# iSENSE_Data_Logger.net
KiCad netlist of a schematic drawn in EAGLE
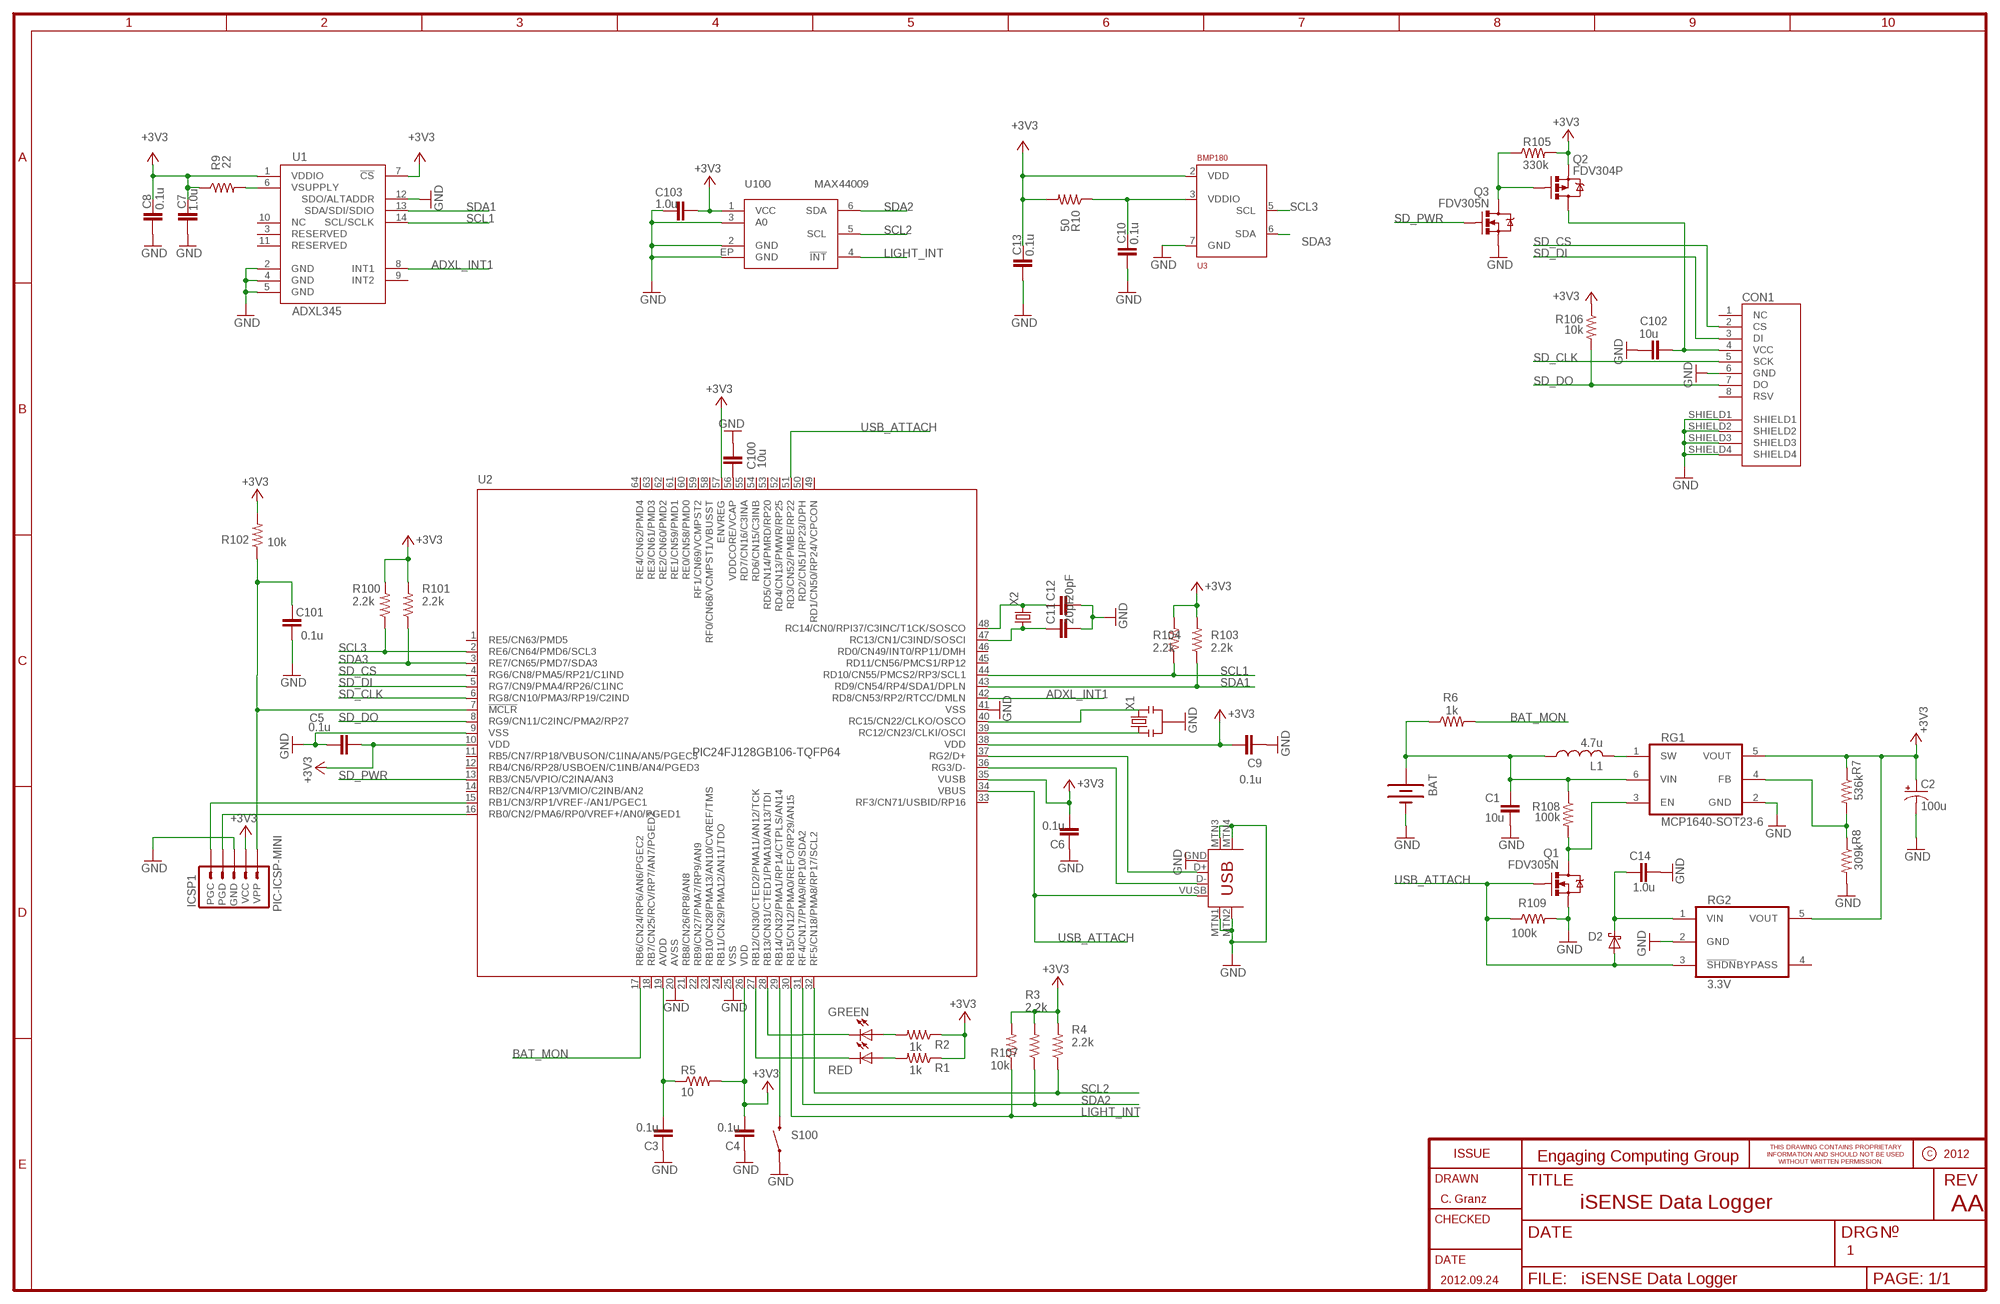
[diagram p0: schematic, sheet 1]

(export (version "E")
  (design (tool "Eeschema 10.0.6"))
  (components
    (comp (ref "BAT")
      (value "BATTERY-AAA-PCB-1-NO-HOLES")
      (footprint "eagle-import:BATTERY_HOLDER_AAA_KEYSTONE_2466_NO_HOLES")
      (libsource (lib "eagle-import") (part "BATTERY-AAA-PCB-1-NO-HOLES"))
    )
    (comp (ref "C1")
      (value "10u")
      (footprint "eagle-import:RCL_0603")
      (libsource (lib "eagle-import") (part "CAPACITOR-0603"))
    )
    (comp (ref "C2")
      (value "100u")
      (footprint "eagle-import:CT3528")
      (libsource (lib "eagle-import") (part "CPOL-USCT3528"))
    )
    (comp (ref "C3")
      (value "0.1u")
      (footprint "eagle-import:RCL_0402")
      (libsource (lib "eagle-import") (part "CAPACITOR-0402"))
    )
    (comp (ref "C4")
      (value "0.1u")
      (footprint "eagle-import:RCL_0402")
      (libsource (lib "eagle-import") (part "CAPACITOR-0402"))
    )
    (comp (ref "C5")
      (value "0.1u")
      (footprint "eagle-import:RCL_0402")
      (libsource (lib "eagle-import") (part "CAPACITOR-0402"))
    )
    (comp (ref "C6")
      (value "0.1u")
      (footprint "eagle-import:RCL_0402")
      (libsource (lib "eagle-import") (part "CAPACITOR-0402"))
    )
    (comp (ref "C7")
      (value "1.0u")
      (footprint "eagle-import:RCL_0402")
      (libsource (lib "eagle-import") (part "CAPACITOR-0402"))
    )
    (comp (ref "C8")
      (value "0.1u")
      (footprint "eagle-import:RCL_0402")
      (libsource (lib "eagle-import") (part "CAPACITOR-0402"))
    )
    (comp (ref "C9")
      (value "0.1u")
      (footprint "eagle-import:RCL_0402")
      (libsource (lib "eagle-import") (part "CAPACITOR-0402"))
    )
    (comp (ref "C10")
      (value "0.1u")
      (footprint "eagle-import:RCL_0402")
      (libsource (lib "eagle-import") (part "CAPACITOR-0402"))
    )
    (comp (ref "C11")
      (value "20pF")
      (footprint "eagle-import:RCL_0402")
      (libsource (lib "eagle-import") (part "CAPACITOR-0402"))
    )
    (comp (ref "C12")
      (value "20pF")
      (footprint "eagle-import:RCL_0402")
      (libsource (lib "eagle-import") (part "CAPACITOR-0402"))
    )
    (comp (ref "C13")
      (value "0.1u")
      (footprint "eagle-import:RCL_0402")
      (libsource (lib "eagle-import") (part "CAPACITOR-0402"))
    )
    (comp (ref "C14")
      (value "1.0u")
      (footprint "eagle-import:RCL_0603")
      (libsource (lib "eagle-import") (part "CAPACITOR-0603"))
    )
    (comp (ref "C100")
      (value "10u")
      (footprint "eagle-import:RCL_0603")
      (libsource (lib "eagle-import") (part "CAPACITOR-0603"))
    )
    (comp (ref "C101")
      (value "0.1u")
      (footprint "eagle-import:RCL_0402")
      (libsource (lib "eagle-import") (part "CAPACITOR-0402"))
    )
    (comp (ref "C102")
      (value "10u")
      (footprint "eagle-import:RCL_0402")
      (libsource (lib "eagle-import") (part "CAPACITOR-0402"))
    )
    (comp (ref "C103")
      (value "1.0u")
      (footprint "eagle-import:RCL_0402")
      (libsource (lib "eagle-import") (part "CAPACITOR-0402"))
    )
    (comp (ref "CON1")
      (value "SOCKET_SD_CARD_MICRO-AMP-101-00303-68")
      (footprint "eagle-import:SOCKET_SD_CARD_MICRO")
      (fields (field (name "PN") "101-00303-68"))
      (libsource (lib "eagle-import") (part "SOCKET_SD_CARD_MICRO-AMP-101-00303-68"))
    )
    (comp (ref "D2")
      (value "DIODE_SCHOTTKY-SOD523")
      (footprint "eagle-import:SOD523")
      (libsource (lib "eagle-import") (part "DIODE_SCHOTTKY-SOD523"))
    )
    (comp (ref "GREEN")
      (value "GREEN")
      (footprint "eagle-import:LED_0603")
      (libsource (lib "eagle-import") (part "LED-0603"))
    )
    (comp (ref "ICSP1")
      (value "PIC-ICSP-MINI")
      (footprint "eagle-import:PIC-ICSP-MINI")
      (libsource (lib "eagle-import") (part "PIC-ICSP-MINI"))
    )
    (comp (ref "L1")
      (value "4.7u")
      (footprint "eagle-import:INDUCTOR_3MM_X_3MM")
      (libsource (lib "eagle-import") (part "INDUCTOR-3X3MM"))
    )
    (comp (ref "Q1")
      (value "FDV305N")
      (footprint "eagle-import:SOT23-3")
      (fields (field (name "PN") "FDV305N"))
      (libsource (lib "eagle-import") (part "FDV305N"))
    )
    (comp (ref "Q2")
      (value "FDV304P")
      (footprint "eagle-import:SOT23-3")
      (fields (field (name "PN") "FDV304P"))
      (libsource (lib "eagle-import") (part "FDV302P"))
    )
    (comp (ref "Q3")
      (value "FDV305N")
      (footprint "eagle-import:SOT23-3")
      (fields (field (name "PN") "FDV305N"))
      (libsource (lib "eagle-import") (part "FDV305N"))
    )
    (comp (ref "R1")
      (value "1k")
      (footprint "eagle-import:RCL_0402")
      (libsource (lib "eagle-import") (part "RESISTOR-0402"))
    )
    (comp (ref "R2")
      (value "1k")
      (footprint "eagle-import:RCL_0402")
      (libsource (lib "eagle-import") (part "RESISTOR-0402"))
    )
    (comp (ref "R3")
      (value "2.2k")
      (footprint "eagle-import:RCL_0402")
      (libsource (lib "eagle-import") (part "RESISTOR-0402"))
    )
    (comp (ref "R4")
      (value "2.2k")
      (footprint "eagle-import:RCL_0402")
      (libsource (lib "eagle-import") (part "RESISTOR-0402"))
    )
    (comp (ref "R5")
      (value "10")
      (footprint "eagle-import:RCL_0402")
      (libsource (lib "eagle-import") (part "RESISTOR-0402"))
    )
    (comp (ref "R6")
      (value "1k")
      (footprint "eagle-import:RCL_0402")
      (libsource (lib "eagle-import") (part "RESISTOR-0402"))
    )
    (comp (ref "R7")
      (value "536k")
      (footprint "eagle-import:RCL_0402")
      (libsource (lib "eagle-import") (part "RESISTOR-0402"))
    )
    (comp (ref "R8")
      (value "309k")
      (footprint "eagle-import:RCL_0402")
      (libsource (lib "eagle-import") (part "RESISTOR-0402"))
    )
    (comp (ref "R9")
      (value "22")
      (footprint "eagle-import:RCL_0402")
      (libsource (lib "eagle-import") (part "RESISTOR-0402"))
    )
    (comp (ref "R10")
      (value "50")
      (footprint "eagle-import:RCL_0402")
      (libsource (lib "eagle-import") (part "RESISTOR-0402"))
    )
    (comp (ref "R100")
      (value "2.2k")
      (footprint "eagle-import:RCL_0402")
      (libsource (lib "eagle-import") (part "RESISTOR-0402"))
    )
    (comp (ref "R101")
      (value "2.2k")
      (footprint "eagle-import:RCL_0402")
      (libsource (lib "eagle-import") (part "RESISTOR-0402"))
    )
    (comp (ref "R102")
      (value "10k")
      (footprint "eagle-import:RCL_0402")
      (libsource (lib "eagle-import") (part "RESISTOR-0402"))
    )
    (comp (ref "R103")
      (value "2.2k")
      (footprint "eagle-import:RCL_0402")
      (libsource (lib "eagle-import") (part "RESISTOR-0402"))
    )
    (comp (ref "R104")
      (value "2.2k")
      (footprint "eagle-import:RCL_0402")
      (libsource (lib "eagle-import") (part "RESISTOR-0402"))
    )
    (comp (ref "R105")
      (value "330k")
      (footprint "eagle-import:RCL_0402")
      (libsource (lib "eagle-import") (part "RESISTOR-0402"))
    )
    (comp (ref "R106")
      (value "10k")
      (footprint "eagle-import:RCL_0402")
      (libsource (lib "eagle-import") (part "RESISTOR-0402"))
    )
    (comp (ref "R107")
      (value "10k")
      (footprint "eagle-import:RCL_0402")
      (libsource (lib "eagle-import") (part "RESISTOR-0402"))
    )
    (comp (ref "R108")
      (value "100k")
      (footprint "eagle-import:RCL_0402")
      (libsource (lib "eagle-import") (part "RESISTOR-0402"))
    )
    (comp (ref "R109")
      (value "100k")
      (footprint "eagle-import:RCL_0402")
      (libsource (lib "eagle-import") (part "RESISTOR-0402"))
    )
    (comp (ref "RED")
      (value "RED")
      (footprint "eagle-import:LED_0603")
      (libsource (lib "eagle-import") (part "LED-0603"))
    )
    (comp (ref "RG1")
      (value "MCP1640-SOT23-6")
      (footprint "eagle-import:SOT23-6")
      (libsource (lib "eagle-import") (part "MCP1640-SOT23-6"))
    )
    (comp (ref "RG2")
      (value "3.3V")
      (footprint "eagle-import:SOT23-5")
      (libsource (lib "eagle-import") (part "TC1015"))
    )
    (comp (ref "S100")
      (value "SWITCH_MOMENTARY-SMD-RA")
      (footprint "eagle-import:SWITCH_TACTILE_SMD_RA")
      (libsource (lib "eagle-import") (part "SWITCH_MOMENTARY-SMD-RA"))
    )
    (comp (ref "U1")
      (value "ADXL345")
      (footprint "eagle-import:LGA14")
      (libsource (lib "eagle-import") (part "ADXL345"))
    )
    (comp (ref "U2")
      (value "PIC24FJ128GB106-TQFP64")
      (footprint "eagle-import:TQFP64-10X10")
      (fields (field (name "PN") "PIC24FJ128GB106-I/PT"))
      (libsource (lib "eagle-import") (part "PIC24FJ128GB106-TQFP64"))
    )
    (comp (ref "U3")
      (value "BMP180")
      (footprint "eagle-import:LGA7")
      (libsource (lib "eagle-import") (part "BMP180"))
    )
    (comp (ref "U100")
      (value "MAX44009")
      (footprint "eagle-import:UTDFN-OPTO")
      (fields (field (name "PN") "MAX44009EDT+T"))
      (libsource (lib "eagle-import") (part "MAX44009"))
    )
    (comp (ref "USB100")
      (value "CON_USB_4_PIN-A_MALE")
      (footprint "eagle-import:CON_USB_A_MALE_CNC_TECH_1001-010-01001")
      (fields (field (name "PN") "1001-010-01001"))
      (libsource (lib "eagle-import") (part "CON_USB_4_PIN-A_MALE"))
    )
    (comp (ref "X1")
      (value "CERAMIC_RESONATOR_3_PIN-2MM_X_4.5MM")
      (footprint "eagle-import:CERAMIC_RESONATOR_MURATA_2X4.5")
      (libsource (lib "eagle-import") (part "CERAMIC_RESONATOR_3_PIN-2MM_X_4.5MM"))
    )
    (comp (ref "X2")
      (value "CRYSTAL_2_PIN-4.9MM_X_1.8MM")
      (footprint "eagle-import:CRYSTAL_ABRACON_ABS10")
      (libsource (lib "eagle-import") (part "CRYSTAL_2_PIN-4.9MM_X_1.8MM"))
    )
  )
  (nets
    (net (code "1") (name "+3V3") (class "Default")
      (node (ref "C103") (pin "1") (pinfunction "1_1") (pintype "passive"))
      (node (ref "C13") (pin "2") (pinfunction "2_2") (pintype "passive"))
      (node (ref "C2") (pin "+") (pinfunction "+_+") (pintype "passive"))
      (node (ref "C4") (pin "2") (pinfunction "2_2") (pintype "passive"))
      (node (ref "C5") (pin "1") (pinfunction "1_1") (pintype "passive"))
      (node (ref "C6") (pin "2") (pinfunction "2_2") (pintype "passive"))
      (node (ref "C7") (pin "2") (pinfunction "2_2") (pintype "passive"))
      (node (ref "C8") (pin "2") (pinfunction "2_2") (pintype "passive"))
      (node (ref "C9") (pin "1") (pinfunction "1_1") (pintype "passive"))
      (node (ref "ICSP1") (pin "2") (pinfunction "VCC_2") (pintype "passive"))
      (node (ref "Q2") (pin "2") (pinfunction "S_2") (pintype "passive"))
      (node (ref "R1") (pin "1") (pinfunction "1_1") (pintype "passive"))
      (node (ref "R10") (pin "2") (pinfunction "2_2") (pintype "passive"))
      (node (ref "R100") (pin "2") (pinfunction "2_2") (pintype "passive"))
      (node (ref "R101") (pin "2") (pinfunction "2_2") (pintype "passive"))
      (node (ref "R102") (pin "2") (pinfunction "2_2") (pintype "passive"))
      (node (ref "R103") (pin "2") (pinfunction "2_2") (pintype "passive"))
      (node (ref "R104") (pin "2") (pinfunction "2_2") (pintype "passive"))
      (node (ref "R105") (pin "2") (pinfunction "2_2") (pintype "passive"))
      (node (ref "R106") (pin "1") (pinfunction "1_1") (pintype "passive"))
      (node (ref "R107") (pin "2") (pinfunction "2_2") (pintype "passive"))
      (node (ref "R2") (pin "1") (pinfunction "1_1") (pintype "passive"))
      (node (ref "R3") (pin "2") (pinfunction "2_2") (pintype "passive"))
      (node (ref "R4") (pin "2") (pinfunction "2_2") (pintype "passive"))
      (node (ref "R5") (pin "2") (pinfunction "2_2") (pintype "passive"))
      (node (ref "R7") (pin "1") (pinfunction "1_1") (pintype "passive"))
      (node (ref "R9") (pin "1") (pinfunction "1_1") (pintype "passive"))
      (node (ref "RG1") (pin "5") (pinfunction "VOUT_5") (pintype "power_in"))
      (node (ref "RG2") (pin "5") (pinfunction "VOUT_5") (pintype "power_in"))
      (node (ref "U1") (pin "1") (pinfunction "VDDIO_1") (pintype "power_in"))
      (node (ref "U1") (pin "7") (pinfunction "~{CS}_7") (pintype "input"))
      (node (ref "U100") (pin "1") (pinfunction "VCC_1") (pintype "bidirectional"))
      (node (ref "U2") (pin "10") (pinfunction "VDD_10") (pintype "power_in"))
      (node (ref "U2") (pin "26") (pinfunction "VDD_26") (pintype "power_in"))
      (node (ref "U2") (pin "35") (pinfunction "VUSB_35") (pintype "bidirectional"))
      (node (ref "U2") (pin "38") (pinfunction "VDD_38") (pintype "power_in"))
      (node (ref "U2") (pin "57") (pinfunction "ENVREG_57") (pintype "bidirectional"))
      (node (ref "U3") (pin "2") (pinfunction "VDD_2") (pintype "power_in"))
    )
    (net (code "2") (name "/ADXL_INT1") (class "Default")
      (node (ref "U1") (pin "8") (pinfunction "INT1_8") (pintype "output"))
      (node (ref "U2") (pin "42") (pinfunction "RD8/CN53/RP2/RTCC/DMLN_42") (pintype "bidirectional"))
    )
    (net (code "3") (name "/BAT_MON") (class "Default")
      (node (ref "R6") (pin "2") (pinfunction "2_2") (pintype "passive"))
      (node (ref "U2") (pin "17") (pinfunction "RB6/CN24/RP6/AN6/PGEC2_17") (pintype "bidirectional"))
    )
    (net (code "4") (name "/LIGHT_INT") (class "Default")
      (node (ref "R107") (pin "1") (pinfunction "1_1") (pintype "passive"))
      (node (ref "U100") (pin "4") (pinfunction "~{INT}_4") (pintype "output"))
      (node (ref "U2") (pin "30") (pinfunction "RB15/CN12/PMA0/REFO/RP29/AN15_30") (pintype "bidirectional"))
    )
    (net (code "5") (name "/SCL1") (class "Default")
      (node (ref "R104") (pin "1") (pinfunction "1_1") (pintype "passive"))
      (node (ref "U1") (pin "14") (pinfunction "SCL/SCLK_14") (pintype "input"))
      (node (ref "U2") (pin "44") (pinfunction "RD10/CN55/PMCS2/RP3/SCL1_44") (pintype "bidirectional"))
    )
    (net (code "6") (name "/SCL2") (class "Default")
      (node (ref "R4") (pin "1") (pinfunction "1_1") (pintype "passive"))
      (node (ref "U100") (pin "5") (pinfunction "SCL_5") (pintype "input"))
      (node (ref "U2") (pin "32") (pinfunction "RF5/CN18/PMA8/RP17/SCL2_32") (pintype "bidirectional"))
    )
    (net (code "7") (name "/SCL3") (class "Default")
      (node (ref "R100") (pin "1") (pinfunction "1_1") (pintype "passive"))
      (node (ref "U2") (pin "2") (pinfunction "RE6/CN64/PMD6/SCL3_2") (pintype "bidirectional"))
      (node (ref "U3") (pin "5") (pinfunction "SCL_5") (pintype "bidirectional"))
    )
    (net (code "8") (name "/SDA1") (class "Default")
      (node (ref "R103") (pin "1") (pinfunction "1_1") (pintype "passive"))
      (node (ref "U1") (pin "13") (pinfunction "SDA/SDI/SDIO_13") (pintype "bidirectional"))
      (node (ref "U2") (pin "43") (pinfunction "RD9/CN54/RP4/SDA1/DPLN_43") (pintype "bidirectional"))
    )
    (net (code "9") (name "/SDA2") (class "Default")
      (node (ref "R3") (pin "1") (pinfunction "1_1") (pintype "passive"))
      (node (ref "U100") (pin "6") (pinfunction "SDA_6") (pintype "bidirectional"))
      (node (ref "U2") (pin "31") (pinfunction "RF4/CN17/PMA9/RP10/SDA2_31") (pintype "bidirectional"))
    )
    (net (code "10") (name "/SDA3") (class "Default")
      (node (ref "R101") (pin "1") (pinfunction "1_1") (pintype "passive"))
      (node (ref "U2") (pin "3") (pinfunction "RE7/CN65/PMD7/SDA3_3") (pintype "bidirectional"))
      (node (ref "U3") (pin "6") (pinfunction "SDA_6") (pintype "bidirectional"))
    )
    (net (code "11") (name "/SD_CLK") (class "Default")
      (node (ref "CON1") (pin "5") (pinfunction "SCK_5") (pintype "input"))
      (node (ref "U2") (pin "6") (pinfunction "RG8/CN10/PMA3/RP19/C2IND_6") (pintype "bidirectional"))
    )
    (net (code "12") (name "/SD_CS") (class "Default")
      (node (ref "CON1") (pin "2") (pinfunction "CS_2") (pintype "input"))
      (node (ref "U2") (pin "4") (pinfunction "RG6/CN8/PMA5/RP21/C1IND_4") (pintype "bidirectional"))
    )
    (net (code "13") (name "/SD_DI") (class "Default")
      (node (ref "CON1") (pin "3") (pinfunction "DI_3") (pintype "input"))
      (node (ref "U2") (pin "5") (pinfunction "RG7/CN9/PMA4/RP26/C1INC_5") (pintype "bidirectional"))
    )
    (net (code "14") (name "/SD_DO") (class "Default")
      (node (ref "CON1") (pin "7") (pinfunction "DO_7") (pintype "output"))
      (node (ref "R106") (pin "2") (pinfunction "2_2") (pintype "passive"))
      (node (ref "U2") (pin "8") (pinfunction "RG9/CN11/C2INC/PMA2/RP27_8") (pintype "bidirectional"))
    )
    (net (code "15") (name "/SD_PWR") (class "Default")
      (node (ref "Q3") (pin "1") (pinfunction "G_1") (pintype "passive"))
      (node (ref "U2") (pin "13") (pinfunction "RB3/CN5/VPIO/C2INA/AN3_13") (pintype "bidirectional"))
    )
    (net (code "16") (name "/USB_ATTACH") (class "Default")
      (node (ref "D2") (pin "A") (pinfunction "A_A") (pintype "passive"))
      (node (ref "Q1") (pin "1") (pinfunction "G_1") (pintype "passive"))
      (node (ref "R109") (pin "1") (pinfunction "1_1") (pintype "passive"))
      (node (ref "RG2") (pin "3") (pinfunction "~{SHDN}_3") (pintype "input"))
      (node (ref "U2") (pin "34") (pinfunction "VBUS_34") (pintype "bidirectional"))
      (node (ref "U2") (pin "51") (pinfunction "RD3/CN52/PMBE/RP22_51") (pintype "bidirectional"))
      (node (ref "USB100") (pin "VUSB") (pinfunction "VBUS_VUSB") (pintype "power_in"))
    )
    (net (code "17") (name "GND") (class "Default")
      (node (ref "BAT") (pin "-") (pinfunction "-_-") (pintype "power_in"))
      (node (ref "C1") (pin "2") (pinfunction "2_2") (pintype "passive"))
      (node (ref "C10") (pin "1") (pinfunction "1_1") (pintype "passive"))
      (node (ref "C100") (pin "2") (pinfunction "2_2") (pintype "passive"))
      (node (ref "C101") (pin "2") (pinfunction "2_2") (pintype "passive"))
      (node (ref "C102") (pin "1") (pinfunction "1_1") (pintype "passive"))
      (node (ref "C103") (pin "2") (pinfunction "2_2") (pintype "passive"))
      (node (ref "C11") (pin "2") (pinfunction "2_2") (pintype "passive"))
      (node (ref "C12") (pin "2") (pinfunction "2_2") (pintype "passive"))
      (node (ref "C13") (pin "1") (pinfunction "1_1") (pintype "passive"))
      (node (ref "C14") (pin "2") (pinfunction "2_2") (pintype "passive"))
      (node (ref "C2") (pin "-") (pinfunction "-_-") (pintype "passive"))
      (node (ref "C3") (pin "1") (pinfunction "1_1") (pintype "passive"))
      (node (ref "C4") (pin "1") (pinfunction "1_1") (pintype "passive"))
      (node (ref "C5") (pin "2") (pinfunction "2_2") (pintype "passive"))
      (node (ref "C6") (pin "1") (pinfunction "1_1") (pintype "passive"))
      (node (ref "C7") (pin "1") (pinfunction "1_1") (pintype "passive"))
      (node (ref "C8") (pin "1") (pinfunction "1_1") (pintype "passive"))
      (node (ref "C9") (pin "2") (pinfunction "2_2") (pintype "passive"))
      (node (ref "CON1") (pin "6") (pinfunction "GND_6") (pintype "power_in"))
      (node (ref "CON1") (pin "SHIELD1") (pinfunction "SHIELD1_SHIELD1") (pintype "passive"))
      (node (ref "CON1") (pin "SHIELD2") (pinfunction "SHIELD2_SHIELD2") (pintype "passive"))
      (node (ref "CON1") (pin "SHIELD3") (pinfunction "SHIELD3_SHIELD3") (pintype "passive"))
      (node (ref "CON1") (pin "SHIELD4") (pinfunction "SHIELD4_SHIELD4") (pintype "passive"))
      (node (ref "ICSP1") (pin "3") (pinfunction "GND_3") (pintype "passive"))
      (node (ref "Q1") (pin "2") (pinfunction "S_2") (pintype "passive"))
      (node (ref "Q3") (pin "2") (pinfunction "S_2") (pintype "passive"))
      (node (ref "R109") (pin "2") (pinfunction "2_2") (pintype "passive"))
      (node (ref "R8") (pin "2") (pinfunction "2_2") (pintype "passive"))
      (node (ref "RG1") (pin "2") (pinfunction "GND_2") (pintype "power_in"))
      (node (ref "RG2") (pin "2") (pinfunction "GND_2") (pintype "power_in"))
      (node (ref "S100") (pin "1") (pinfunction "1_1") (pintype "passive"))
      (node (ref "U1") (pin "12") (pinfunction "SDO/ALTADDR_12") (pintype "bidirectional"))
      (node (ref "U1") (pin "2") (pinfunction "GND_2") (pintype "power_in"))
      (node (ref "U1") (pin "4") (pinfunction "GND_4") (pintype "power_in"))
      (node (ref "U1") (pin "5") (pinfunction "GND_5") (pintype "power_in"))
      (node (ref "U100") (pin "2") (pinfunction "GND_2") (pintype "power_in"))
      (node (ref "U100") (pin "3") (pinfunction "A0_3") (pintype "bidirectional"))
      (node (ref "U100") (pin "EP") (pinfunction "GND_EP") (pintype "power_in"))
      (node (ref "U2") (pin "20") (pinfunction "AVSS_20") (pintype "power_in"))
      (node (ref "U2") (pin "25") (pinfunction "VSS_25") (pintype "power_in"))
      (node (ref "U2") (pin "41") (pinfunction "VSS_41") (pintype "power_in"))
      (node (ref "U2") (pin "9") (pinfunction "VSS_9") (pintype "power_in"))
      (node (ref "U3") (pin "7") (pinfunction "GND_7") (pintype "power_in"))
      (node (ref "USB100") (pin "GND") (pinfunction "GND_GND") (pintype "power_in"))
      (node (ref "USB100") (pin "MTN1") (pinfunction "MTN1_MTN1") (pintype "passive"))
      (node (ref "USB100") (pin "MTN2") (pinfunction "MTN2_MTN2") (pintype "passive"))
      (node (ref "USB100") (pin "MTN3") (pinfunction "MTN3_MTN3") (pintype "passive"))
      (node (ref "USB100") (pin "MTN4") (pinfunction "MTN4_MTN4") (pintype "passive"))
      (node (ref "X1") (pin "2") (pinfunction "2_2") (pintype "passive"))
    )
    (net (code "18") (name "Net-(CON1-VCC)") (class "Default")
      (node (ref "C102") (pin "2") (pinfunction "2_2") (pintype "passive"))
      (node (ref "CON1") (pin "4") (pinfunction "VCC_4") (pintype "power_in"))
      (node (ref "Q2") (pin "3") (pinfunction "D_3") (pintype "passive"))
    )
    (net (code "19") (name "Net-(GREEN-PadA)") (class "Default")
      (node (ref "GREEN") (pin "A") (pinfunction "A_A") (pintype "passive"))
      (node (ref "R2") (pin "2") (pinfunction "2_2") (pintype "passive"))
    )
    (net (code "20") (name "Net-(ICSP1-PGC)") (class "Default")
      (node (ref "ICSP1") (pin "5") (pinfunction "PGC_5") (pintype "passive"))
      (node (ref "U2") (pin "15") (pinfunction "RB1/CN3/RP1/VREF-/AN1/PGEC1_15") (pintype "bidirectional"))
    )
    (net (code "21") (name "Net-(ICSP1-PGD)") (class "Default")
      (node (ref "ICSP1") (pin "4") (pinfunction "PGD_4") (pintype "passive"))
      (node (ref "U2") (pin "16") (pinfunction "RB0/CN2/PMA6/RP0/VREF+/AN0/PGED1_16") (pintype "bidirectional"))
    )
    (net (code "22") (name "Net-(ICSP1-VPP)") (class "Default")
      (node (ref "C101") (pin "1") (pinfunction "1_1") (pintype "passive"))
      (node (ref "ICSP1") (pin "1") (pinfunction "VPP_1") (pintype "passive"))
      (node (ref "R102") (pin "1") (pinfunction "1_1") (pintype "passive"))
      (node (ref "U2") (pin "7") (pinfunction "~{MCLR}_7") (pintype "bidirectional"))
    )
    (net (code "23") (name "Net-(Q1-D)") (class "Default")
      (node (ref "Q1") (pin "3") (pinfunction "D_3") (pintype "passive"))
      (node (ref "R108") (pin "2") (pinfunction "2_2") (pintype "passive"))
      (node (ref "RG1") (pin "3") (pinfunction "EN_3") (pintype "input"))
    )
    (net (code "24") (name "Net-(Q2-G)") (class "Default")
      (node (ref "Q2") (pin "1") (pinfunction "G_1") (pintype "passive"))
      (node (ref "Q3") (pin "3") (pinfunction "D_3") (pintype "passive"))
      (node (ref "R105") (pin "1") (pinfunction "1_1") (pintype "passive"))
    )
    (net (code "25") (name "Net-(R1-Pad2)") (class "Default")
      (node (ref "R1") (pin "2") (pinfunction "2_2") (pintype "passive"))
      (node (ref "RED") (pin "A") (pinfunction "A_A") (pintype "passive"))
    )
    (net (code "26") (name "Net-(RG1-FB)") (class "Default")
      (node (ref "R7") (pin "2") (pinfunction "2_2") (pintype "passive"))
      (node (ref "R8") (pin "1") (pinfunction "1_1") (pintype "passive"))
      (node (ref "RG1") (pin "4") (pinfunction "FB_4") (pintype "input"))
    )
    (net (code "27") (name "Net-(RG1-SW)") (class "Default")
      (node (ref "L1") (pin "2") (pinfunction "2_2") (pintype "passive"))
      (node (ref "RG1") (pin "1") (pinfunction "SW_1") (pintype "passive"))
    )
    (net (code "28") (name "Net-(RG1-VIN)") (class "Default")
      (node (ref "BAT") (pin "+") (pinfunction "+_+") (pintype "power_in"))
      (node (ref "C1") (pin "1") (pinfunction "1_1") (pintype "passive"))
      (node (ref "L1") (pin "1") (pinfunction "1_1") (pintype "passive"))
      (node (ref "R108") (pin "1") (pinfunction "1_1") (pintype "passive"))
      (node (ref "R6") (pin "1") (pinfunction "1_1") (pintype "passive"))
      (node (ref "RG1") (pin "6") (pinfunction "VIN_6") (pintype "power_in"))
    )
    (net (code "29") (name "Net-(RG2-VIN)") (class "Default")
      (node (ref "C14") (pin "1") (pinfunction "1_1") (pintype "passive"))
      (node (ref "D2") (pin "C") (pinfunction "C_C") (pintype "passive"))
      (node (ref "RG2") (pin "1") (pinfunction "VIN_1") (pintype "power_in"))
    )
    (net (code "30") (name "Net-(U1-VSUPPLY)") (class "Default")
      (node (ref "R9") (pin "2") (pinfunction "2_2") (pintype "passive"))
      (node (ref "U1") (pin "6") (pinfunction "VSUPPLY_6") (pintype "power_in"))
    )
    (net (code "31") (name "Net-(U2-AVDD)") (class "Default")
      (node (ref "C3") (pin "2") (pinfunction "2_2") (pintype "passive"))
      (node (ref "R5") (pin "1") (pinfunction "1_1") (pintype "passive"))
      (node (ref "U2") (pin "19") (pinfunction "AVDD_19") (pintype "power_in"))
    )
    (net (code "32") (name "Net-(U2-RB12{slash}CN30{slash}CTED2{slash}PMA11{slash}AN12{slash}TCK)") (class "Default")
      (node (ref "RED") (pin "C") (pinfunction "C_C") (pintype "passive"))
      (node (ref "U2") (pin "27") (pinfunction "RB12/CN30/CTED2/PMA11/AN12/TCK_27") (pintype "bidirectional"))
    )
    (net (code "33") (name "Net-(U2-RB13{slash}CN31{slash}CTED1{slash}PMA10{slash}AN13{slash}TDI)") (class "Default")
      (node (ref "GREEN") (pin "C") (pinfunction "C_C") (pintype "passive"))
      (node (ref "U2") (pin "28") (pinfunction "RB13/CN31/CTED1/PMA10/AN13/TDI_28") (pintype "bidirectional"))
    )
    (net (code "34") (name "Net-(U2-RB14{slash}CN32{slash}PMA1{slash}RP14{slash}CTPLS{slash}AN14)") (class "Default")
      (node (ref "S100") (pin "2") (pinfunction "2_2") (pintype "passive"))
      (node (ref "U2") (pin "29") (pinfunction "RB14/CN32/PMA1/RP14/CTPLS/AN14_29") (pintype "bidirectional"))
    )
    (net (code "35") (name "Net-(U2-RC12{slash}CN23{slash}CLKI{slash}OSCI)") (class "Default")
      (node (ref "U2") (pin "39") (pinfunction "RC12/CN23/CLKI/OSCI_39") (pintype "bidirectional"))
      (node (ref "X1") (pin "1") (pinfunction "1_1") (pintype "passive"))
    )
    (net (code "36") (name "Net-(U2-RC13{slash}CN1{slash}C3IND{slash}SOSCI)") (class "Default")
      (node (ref "C11") (pin "1") (pinfunction "1_1") (pintype "passive"))
      (node (ref "U2") (pin "47") (pinfunction "RC13/CN1/C3IND/SOSCI_47") (pintype "bidirectional"))
      (node (ref "X2") (pin "1") (pinfunction "1_1") (pintype "passive"))
    )
    (net (code "37") (name "Net-(U2-RC14{slash}CN0{slash}RPI37{slash}C3INC{slash}T1CK{slash}SOSCO)") (class "Default")
      (node (ref "C12") (pin "1") (pinfunction "1_1") (pintype "passive"))
      (node (ref "U2") (pin "48") (pinfunction "RC14/CN0/RPI37/C3INC/T1CK/SOSCO_48") (pintype "bidirectional"))
      (node (ref "X2") (pin "2") (pinfunction "2_2") (pintype "passive"))
    )
    (net (code "38") (name "Net-(U2-RC15{slash}CN22{slash}CLKO{slash}OSCO)") (class "Default")
      (node (ref "U2") (pin "40") (pinfunction "RC15/CN22/CLKO/OSCO_40") (pintype "bidirectional"))
      (node (ref "X1") (pin "3") (pinfunction "3_3") (pintype "passive"))
    )
    (net (code "39") (name "Net-(U2-RG2{slash}D+)") (class "Default")
      (node (ref "U2") (pin "37") (pinfunction "RG2/D+_37") (pintype "bidirectional"))
      (node (ref "USB100") (pin "D+") (pinfunction "D+_D+") (pintype "bidirectional"))
    )
    (net (code "40") (name "Net-(U2-RG3{slash}D-)") (class "Default")
      (node (ref "U2") (pin "36") (pinfunction "RG3/D-_36") (pintype "bidirectional"))
      (node (ref "USB100") (pin "D-") (pinfunction "D-_D-") (pintype "bidirectional"))
    )
    (net (code "41") (name "Net-(U2-VDDCORE{slash}VCAP)") (class "Default")
      (node (ref "C100") (pin "1") (pinfunction "1_1") (pintype "passive"))
      (node (ref "U2") (pin "56") (pinfunction "VDDCORE/VCAP_56") (pintype "bidirectional"))
    )
    (net (code "42") (name "Net-(U3-VDDIO)") (class "Default")
      (node (ref "C10") (pin "2") (pinfunction "2_2") (pintype "passive"))
      (node (ref "R10") (pin "1") (pinfunction "1_1") (pintype "passive"))
      (node (ref "U3") (pin "3") (pinfunction "VDDIO_3") (pintype "power_in"))
    )
    (net (code "43") (name "unconnected-(CON1-NC-Pad1)") (class "Default")
      (node (ref "CON1") (pin "1") (pinfunction "NC_1") (pintype "no_connect"))
    )
    (net (code "44") (name "unconnected-(CON1-RSV-Pad8)") (class "Default")
      (node (ref "CON1") (pin "8") (pinfunction "RSV_8") (pintype "no_connect"))
    )
    (net (code "45") (name "unconnected-(RG2-BYPASS-Pad4)") (class "Default")
      (node (ref "RG2") (pin "4") (pinfunction "BYPASS_4") (pintype "passive"))
    )
    (net (code "46") (name "unconnected-(U1-INT2-Pad9)") (class "Default")
      (node (ref "U1") (pin "9") (pinfunction "INT2_9") (pintype "output"))
    )
    (net (code "47") (name "unconnected-(U1-NC-Pad10)") (class "Default")
      (node (ref "U1") (pin "10") (pinfunction "NC_10") (pintype "no_connect"))
    )
    (net (code "48") (name "unconnected-(U1-RESERVED-Pad3)") (class "Default")
      (node (ref "U1") (pin "3") (pinfunction "RESERVED_3") (pintype "passive"))
    )
    (net (code "49") (name "unconnected-(U1-RESERVED-Pad11)") (class "Default")
      (node (ref "U1") (pin "11") (pinfunction "RESERVED_11") (pintype "passive"))
    )
    (net (code "50") (name "unconnected-(U2-RB2{slash}CN4{slash}RP13{slash}VMIO{slash}C2INB{slash}AN2-Pad14)") (class "Default")
      (node (ref "U2") (pin "14") (pinfunction "RB2/CN4/RP13/VMIO/C2INB/AN2_14") (pintype "bidirectional"))
    )
    (net (code "51") (name "unconnected-(U2-RB4{slash}CN6{slash}RP28{slash}USBOEN{slash}C1INB{slash}AN4{slash}PGED3-Pad12)") (class "Default")
      (node (ref "U2") (pin "12") (pinfunction "RB4/CN6/RP28/USBOEN/C1INB/AN4/PGED3_12") (pintype "bidirectional"))
    )
    (net (code "52") (name "unconnected-(U2-RB5{slash}CN7{slash}RP18{slash}VBUSON{slash}C1INA{slash}AN5{slash}PGEC3-Pad11)") (class "Default")
      (node (ref "U2") (pin "11") (pinfunction "RB5/CN7/RP18/VBUSON/C1INA/AN5/PGEC3_11") (pintype "bidirectional"))
    )
    (net (code "53") (name "unconnected-(U2-RB7{slash}CN25{slash}RCV{slash}RP7{slash}AN7{slash}PGED2-Pad18)") (class "Default")
      (node (ref "U2") (pin "18") (pinfunction "RB7/CN25/RCV/RP7/AN7/PGED2_18") (pintype "bidirectional"))
    )
    (net (code "54") (name "unconnected-(U2-RB8{slash}CN26{slash}RP8{slash}AN8-Pad21)") (class "Default")
      (node (ref "U2") (pin "21") (pinfunction "RB8/CN26/RP8/AN8_21") (pintype "bidirectional"))
    )
    (net (code "55") (name "unconnected-(U2-RB9{slash}CN27{slash}PMA7{slash}RP9{slash}AN9-Pad22)") (class "Default")
      (node (ref "U2") (pin "22") (pinfunction "RB9/CN27/PMA7/RP9/AN9_22") (pintype "bidirectional"))
    )
    (net (code "56") (name "unconnected-(U2-RB10{slash}CN28{slash}PMA13{slash}AN10{slash}CVREF{slash}TMS-Pad23)") (class "Default")
      (node (ref "U2") (pin "23") (pinfunction "RB10/CN28/PMA13/AN10/CVREF/TMS_23") (pintype "bidirectional"))
    )
    (net (code "57") (name "unconnected-(U2-RB11{slash}CN29{slash}PMA12{slash}AN11{slash}TDO-Pad24)") (class "Default")
      (node (ref "U2") (pin "24") (pinfunction "RB11/CN29/PMA12/AN11/TDO_24") (pintype "bidirectional"))
    )
    (net (code "58") (name "unconnected-(U2-RD0{slash}CN49{slash}INT0{slash}RP11{slash}DMH-Pad46)") (class "Default")
      (node (ref "U2") (pin "46") (pinfunction "RD0/CN49/INT0/RP11/DMH_46") (pintype "bidirectional"))
    )
    (net (code "59") (name "unconnected-(U2-RD1{slash}CN50{slash}RP24{slash}VCPCON-Pad49)") (class "Default")
      (node (ref "U2") (pin "49") (pinfunction "RD1/CN50/RP24/VCPCON_49") (pintype "bidirectional"))
    )
    (net (code "60") (name "unconnected-(U2-RD2{slash}CN51{slash}RP23{slash}DPH-Pad50)") (class "Default")
      (node (ref "U2") (pin "50") (pinfunction "RD2/CN51/RP23/DPH_50") (pintype "bidirectional"))
    )
    (net (code "61") (name "unconnected-(U2-RD4{slash}CN13{slash}PMWR{slash}RP25-Pad52)") (class "Default")
      (node (ref "U2") (pin "52") (pinfunction "RD4/CN13/PMWR/RP25_52") (pintype "bidirectional"))
    )
    (net (code "62") (name "unconnected-(U2-RD5{slash}CN14{slash}PMRD{slash}RP20-Pad53)") (class "Default")
      (node (ref "U2") (pin "53") (pinfunction "RD5/CN14/PMRD/RP20_53") (pintype "bidirectional"))
    )
    (net (code "63") (name "unconnected-(U2-RD6{slash}CN15{slash}C3INB-Pad54)") (class "Default")
      (node (ref "U2") (pin "54") (pinfunction "RD6/CN15/C3INB_54") (pintype "bidirectional"))
    )
    (net (code "64") (name "unconnected-(U2-RD7{slash}CN16{slash}C3INA-Pad55)") (class "Default")
      (node (ref "U2") (pin "55") (pinfunction "RD7/CN16/C3INA_55") (pintype "bidirectional"))
    )
    (net (code "65") (name "unconnected-(U2-RD11{slash}CN56{slash}PMCS1{slash}RP12-Pad45)") (class "Default")
      (node (ref "U2") (pin "45") (pinfunction "RD11/CN56/PMCS1/RP12_45") (pintype "bidirectional"))
    )
    (net (code "66") (name "unconnected-(U2-RE0{slash}CN58{slash}PMD0-Pad60)") (class "Default")
      (node (ref "U2") (pin "60") (pinfunction "RE0/CN58/PMD0_60") (pintype "bidirectional"))
    )
    (net (code "67") (name "unconnected-(U2-RE1{slash}CN59{slash}PMD1-Pad61)") (class "Default")
      (node (ref "U2") (pin "61") (pinfunction "RE1/CN59/PMD1_61") (pintype "bidirectional"))
    )
    (net (code "68") (name "unconnected-(U2-RE2{slash}CN60{slash}PMD2-Pad62)") (class "Default")
      (node (ref "U2") (pin "62") (pinfunction "RE2/CN60/PMD2_62") (pintype "bidirectional"))
    )
    (net (code "69") (name "unconnected-(U2-RE3{slash}CN61{slash}PMD3-Pad63)") (class "Default")
      (node (ref "U2") (pin "63") (pinfunction "RE3/CN61/PMD3_63") (pintype "bidirectional"))
    )
    (net (code "70") (name "unconnected-(U2-RE4{slash}CN62{slash}PMD4-Pad64)") (class "Default")
      (node (ref "U2") (pin "64") (pinfunction "RE4/CN62/PMD4_64") (pintype "bidirectional"))
    )
    (net (code "71") (name "unconnected-(U2-RE5{slash}CN63{slash}PMD5-Pad1)") (class "Default")
      (node (ref "U2") (pin "1") (pinfunction "RE5/CN63/PMD5_1") (pintype "bidirectional"))
    )
    (net (code "72") (name "unconnected-(U2-RF0{slash}CN68{slash}VCMPST1{slash}VBUSST-Pad58)") (class "Default")
      (node (ref "U2") (pin "58") (pinfunction "RF0/CN68/VCMPST1/VBUSST_58") (pintype "bidirectional"))
    )
    (net (code "73") (name "unconnected-(U2-RF1{slash}CN69{slash}VCMPST2-Pad59)") (class "Default")
      (node (ref "U2") (pin "59") (pinfunction "RF1/CN69/VCMPST2_59") (pintype "bidirectional"))
    )
    (net (code "74") (name "unconnected-(U2-RF3{slash}CN71{slash}USBID{slash}RP16-Pad33)") (class "Default")
      (node (ref "U2") (pin "33") (pinfunction "RF3/CN71/USBID/RP16_33") (pintype "bidirectional"))
    )
    (net (code "75") (name "unconnected-(U3-P$1-Pad1)") (class "Default")
      (node (ref "U3") (pin "1") (pinfunction "P$1_1") (pintype "no_connect"))
    )
    (net (code "76") (name "unconnected-(U3-P$2-Pad4)") (class "Default")
      (node (ref "U3") (pin "4") (pinfunction "P$2_4") (pintype "no_connect"))
    )
  )
)
